# ds1307.net
KiCad netlist of a schematic drawn in EAGLE
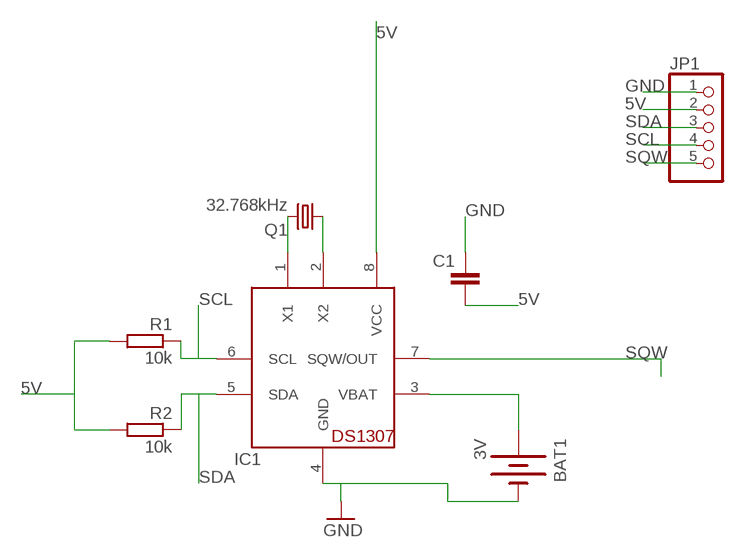
[diagram p0: schematic, sheet 1]

(export (version "E")
  (design (tool "Eeschema 10.0.6"))
  (components
    (comp (ref "BAT1")
      (value "3V")
      (footprint "eagle-import:BATTCOM_20MM_PTH")
      (libsource (lib "eagle-import") (part "BATTERY20PTH"))
    )
    (comp (ref "C1")
      (value "C-EUC1206")
      (footprint "eagle-import:C1206")
      (libsource (lib "eagle-import") (part "C-EUC1206"))
    )
    (comp (ref "IC1")
      (value "DS1307")
      (footprint "eagle-import:DIL08")
      (libsource (lib "eagle-import") (part "DS1307"))
    )
    (comp (ref "JP1")
      (value "PINHD-1X5")
      (footprint "eagle-import:1X05")
      (libsource (lib "eagle-import") (part "PINHD-1X5"))
    )
    (comp (ref "Q1")
      (value "32.768kHz")
      (footprint "eagle-import:TC38H")
      (libsource (lib "eagle-import") (part "CRYSTALTC38H"))
    )
    (comp (ref "R1")
      (value "10k")
      (footprint "eagle-import:R1206")
      (libsource (lib "eagle-import") (part "R-EU_R1206"))
    )
    (comp (ref "R2")
      (value "10k")
      (footprint "eagle-import:R1206")
      (libsource (lib "eagle-import") (part "R-EU_R1206"))
    )
  )
  (nets
    (net (code "1") (name "/5V") (class "Default")
      (node (ref "C1") (pin "2") (pinfunction "2_2") (pintype "passive"))
      (node (ref "IC1") (pin "8") (pinfunction "VCC_8") (pintype "power_in"))
      (node (ref "JP1") (pin "2") (pinfunction "2_2") (pintype "passive"))
      (node (ref "R1") (pin "2") (pinfunction "2_2") (pintype "passive"))
      (node (ref "R2") (pin "2") (pinfunction "2_2") (pintype "passive"))
    )
    (net (code "2") (name "/SCL") (class "Default")
      (node (ref "IC1") (pin "6") (pinfunction "SCL_6") (pintype "bidirectional"))
      (node (ref "JP1") (pin "4") (pinfunction "4_4") (pintype "passive"))
      (node (ref "R1") (pin "1") (pinfunction "1_1") (pintype "passive"))
    )
    (net (code "3") (name "/SDA") (class "Default")
      (node (ref "IC1") (pin "5") (pinfunction "SDA_5") (pintype "bidirectional"))
      (node (ref "JP1") (pin "3") (pinfunction "3_3") (pintype "passive"))
      (node (ref "R2") (pin "1") (pinfunction "1_1") (pintype "passive"))
    )
    (net (code "4") (name "/SQW") (class "Default")
      (node (ref "IC1") (pin "7") (pinfunction "SQW/OUT_7") (pintype "bidirectional"))
      (node (ref "JP1") (pin "5") (pinfunction "5_5") (pintype "passive"))
    )
    (net (code "5") (name "GND") (class "Default")
      (node (ref "BAT1") (pin "2") (pinfunction "-_2") (pintype "power_in"))
      (node (ref "C1") (pin "1") (pinfunction "1_1") (pintype "passive"))
      (node (ref "IC1") (pin "4") (pinfunction "GND_4") (pintype "power_in"))
      (node (ref "JP1") (pin "1") (pinfunction "1_1") (pintype "passive"))
    )
    (net (code "6") (name "Net-(BAT1-+)") (class "Default")
      (node (ref "BAT1") (pin "1") (pinfunction "+_1") (pintype "power_in"))
      (node (ref "IC1") (pin "3") (pinfunction "VBAT_3") (pintype "power_in"))
    )
    (net (code "7") (name "Net-(IC1-X1)") (class "Default")
      (node (ref "IC1") (pin "1") (pinfunction "X1_1") (pintype "passive"))
      (node (ref "Q1") (pin "2") (pinfunction "2_2") (pintype "passive"))
    )
    (net (code "8") (name "Net-(IC1-X2)") (class "Default")
      (node (ref "IC1") (pin "2") (pinfunction "X2_2") (pintype "passive"))
      (node (ref "Q1") (pin "1") (pinfunction "1_1") (pintype "passive"))
    )
  )
)
